# lv_io_analog_input.net
KiCad netlist of a schematic drawn in Altium Designer
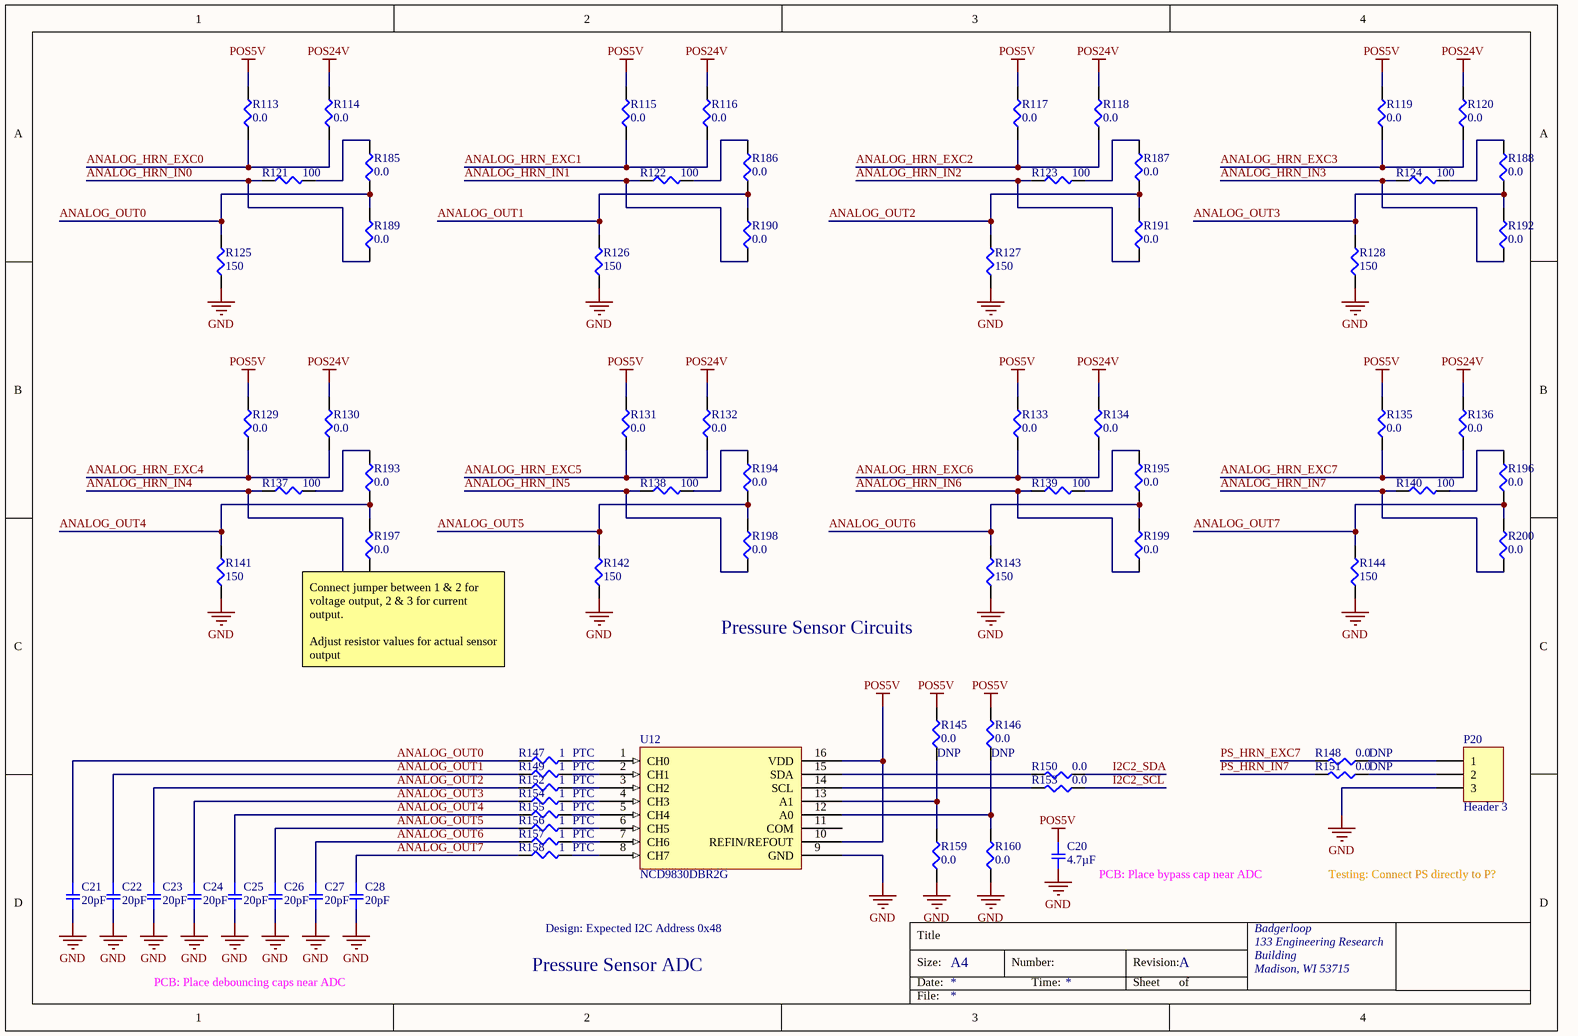
[diagram p0: lv_io_analog_input.SchDoc]

(export (version "E")
  (design (tool "Eeschema 10.0.6"))
  (components
    (comp (ref "C20")
      (value "4.7µF")
      (footprint "SMD-0805C")
      (description "CAP CER 4.7UF 6.3V X5R 0805")
      (fields
        (field (name "DIGI-KEY PART NUMBER") "490-9749-1-ND")
        (field (name "PART NUMBER") "GRM21BR60J475KA11L")
      )
      (libsource (lib "capacitor") (part "GRM21BR60J475KA11L"))
    )
    (comp (ref "C21")
      (value "20pF")
      (footprint "SMD-0402C")
      (description "CAP CER 20PF 50V NP0 0402")
      (fields
        (field (name "DIGI-KEY PART NUMBER") "490-3120-1-ND")
        (field (name "PART NUMBER") "GJM1555C1H200JB01D")
      )
      (libsource (lib "capacitor") (part "GJM1555C1H200JB01D"))
    )
    (comp (ref "C22")
      (value "20pF")
      (footprint "SMD-0402C")
      (description "CAP CER 20PF 50V NP0 0402")
      (fields
        (field (name "DIGI-KEY PART NUMBER") "490-3120-1-ND")
        (field (name "PART NUMBER") "GJM1555C1H200JB01D")
      )
      (libsource (lib "capacitor") (part "GJM1555C1H200JB01D"))
    )
    (comp (ref "C23")
      (value "20pF")
      (footprint "SMD-0402C")
      (description "CAP CER 20PF 50V NP0 0402")
      (fields
        (field (name "DIGI-KEY PART NUMBER") "490-3120-1-ND")
        (field (name "PART NUMBER") "GJM1555C1H200JB01D")
      )
      (libsource (lib "capacitor") (part "GJM1555C1H200JB01D"))
    )
    (comp (ref "C24")
      (value "20pF")
      (footprint "SMD-0402C")
      (description "CAP CER 20PF 50V NP0 0402")
      (fields
        (field (name "DIGI-KEY PART NUMBER") "490-3120-1-ND")
        (field (name "PART NUMBER") "GJM1555C1H200JB01D")
      )
      (libsource (lib "capacitor") (part "GJM1555C1H200JB01D"))
    )
    (comp (ref "C25")
      (value "20pF")
      (footprint "SMD-0402C")
      (description "CAP CER 20PF 50V NP0 0402")
      (fields
        (field (name "DIGI-KEY PART NUMBER") "490-3120-1-ND")
        (field (name "PART NUMBER") "GJM1555C1H200JB01D")
      )
      (libsource (lib "capacitor") (part "GJM1555C1H200JB01D"))
    )
    (comp (ref "C26")
      (value "20pF")
      (footprint "SMD-0402C")
      (description "CAP CER 20PF 50V NP0 0402")
      (fields
        (field (name "DIGI-KEY PART NUMBER") "490-3120-1-ND")
        (field (name "PART NUMBER") "GJM1555C1H200JB01D")
      )
      (libsource (lib "capacitor") (part "GJM1555C1H200JB01D"))
    )
    (comp (ref "C27")
      (value "20pF")
      (footprint "SMD-0402C")
      (description "CAP CER 20PF 50V NP0 0402")
      (fields
        (field (name "DIGI-KEY PART NUMBER") "490-3120-1-ND")
        (field (name "PART NUMBER") "GJM1555C1H200JB01D")
      )
      (libsource (lib "capacitor") (part "GJM1555C1H200JB01D"))
    )
    (comp (ref "C28")
      (value "20pF")
      (footprint "SMD-0402C")
      (description "CAP CER 20PF 50V NP0 0402")
      (fields
        (field (name "DIGI-KEY PART NUMBER") "490-3120-1-ND")
        (field (name "PART NUMBER") "GJM1555C1H200JB01D")
      )
      (libsource (lib "capacitor") (part "GJM1555C1H200JB01D"))
    )
    (comp (ref "P20")
      (value "Header 3")
      (footprint "Pin Header 1x3 TH Pitch 2.54mm")
      (description "Header, 3-Pin")
      (fields (field (name "PUBLISHER") "Altium Limited"))
      (libsource (lib "connector") (part "Header 3"))
    )
    (comp (ref "R113")
      (value "0.0")
      (footprint "SMD-0402-RES")
      (description "RES SMD 0.0OHM JUMPER 1/10W 0402")
      (fields (field (name "PART NUMBER") "ERJ-2GE0R00X") (field (name "DIGI-KEY PART NUMBER") "P0.0JCT-ND"))
      (libsource (lib "resistor") (part "ERJ-2GE0R00X"))
    )
    (comp (ref "R114")
      (value "0.0")
      (footprint "SMD-0402-RES")
      (description "RES SMD 0.0OHM JUMPER 1/10W 0402")
      (fields (field (name "PART NUMBER") "ERJ-2GE0R00X") (field (name "DIGI-KEY PART NUMBER") "P0.0JCT-ND"))
      (libsource (lib "resistor") (part "ERJ-2GE0R00X"))
    )
    (comp (ref "R115")
      (value "0.0")
      (footprint "SMD-0402-RES")
      (description "RES SMD 0.0OHM JUMPER 1/10W 0402")
      (fields (field (name "PART NUMBER") "ERJ-2GE0R00X") (field (name "DIGI-KEY PART NUMBER") "P0.0JCT-ND"))
      (libsource (lib "resistor") (part "ERJ-2GE0R00X"))
    )
    (comp (ref "R116")
      (value "0.0")
      (footprint "SMD-0402-RES")
      (description "RES SMD 0.0OHM JUMPER 1/10W 0402")
      (fields (field (name "PART NUMBER") "ERJ-2GE0R00X") (field (name "DIGI-KEY PART NUMBER") "P0.0JCT-ND"))
      (libsource (lib "resistor") (part "ERJ-2GE0R00X"))
    )
    (comp (ref "R117")
      (value "0.0")
      (footprint "SMD-0402-RES")
      (description "RES SMD 0.0OHM JUMPER 1/10W 0402")
      (fields (field (name "PART NUMBER") "ERJ-2GE0R00X") (field (name "DIGI-KEY PART NUMBER") "P0.0JCT-ND"))
      (libsource (lib "resistor") (part "ERJ-2GE0R00X"))
    )
    (comp (ref "R118")
      (value "0.0")
      (footprint "SMD-0402-RES")
      (description "RES SMD 0.0OHM JUMPER 1/10W 0402")
      (fields (field (name "PART NUMBER") "ERJ-2GE0R00X") (field (name "DIGI-KEY PART NUMBER") "P0.0JCT-ND"))
      (libsource (lib "resistor") (part "ERJ-2GE0R00X"))
    )
    (comp (ref "R119")
      (value "0.0")
      (footprint "SMD-0402-RES")
      (description "RES SMD 0.0OHM JUMPER 1/10W 0402")
      (fields (field (name "PART NUMBER") "ERJ-2GE0R00X") (field (name "DIGI-KEY PART NUMBER") "P0.0JCT-ND"))
      (libsource (lib "resistor") (part "ERJ-2GE0R00X"))
    )
    (comp (ref "R120")
      (value "0.0")
      (footprint "SMD-0402-RES")
      (description "RES SMD 0.0OHM JUMPER 1/10W 0402")
      (fields (field (name "PART NUMBER") "ERJ-2GE0R00X") (field (name "DIGI-KEY PART NUMBER") "P0.0JCT-ND"))
      (libsource (lib "resistor") (part "ERJ-2GE0R00X"))
    )
    (comp (ref "R121")
      (value "100")
      (footprint "SMD-0402-RES")
      (description "RES SMD 100 OHM 5% 1/10W 0402")
      (fields (field (name "PART NUMBER") "ERJ-2GEJ101X") (field (name "DIGI-KEY PART NUMBER") "P100JCT-ND"))
      (libsource (lib "resistor") (part "ERJ-2GEJ101X"))
    )
    (comp (ref "R122")
      (value "100")
      (footprint "SMD-0402-RES")
      (description "RES SMD 100 OHM 5% 1/10W 0402")
      (fields (field (name "PART NUMBER") "ERJ-2GEJ101X") (field (name "DIGI-KEY PART NUMBER") "P100JCT-ND"))
      (libsource (lib "resistor") (part "ERJ-2GEJ101X"))
    )
    (comp (ref "R123")
      (value "100")
      (footprint "SMD-0402-RES")
      (description "RES SMD 100 OHM 5% 1/10W 0402")
      (fields (field (name "PART NUMBER") "ERJ-2GEJ101X") (field (name "DIGI-KEY PART NUMBER") "P100JCT-ND"))
      (libsource (lib "resistor") (part "ERJ-2GEJ101X"))
    )
    (comp (ref "R124")
      (value "100")
      (footprint "SMD-0402-RES")
      (description "RES SMD 100 OHM 5% 1/10W 0402")
      (fields (field (name "PART NUMBER") "ERJ-2GEJ101X") (field (name "DIGI-KEY PART NUMBER") "P100JCT-ND"))
      (libsource (lib "resistor") (part "ERJ-2GEJ101X"))
    )
    (comp (ref "R125")
      (value "150")
      (footprint "SMD-0603-RES")
      (description "RES SMD 150 OHM 0.5% 1/5W 0603")
      (fields
        (field (name "PART NUMBER") "ERJ-P03D1500V")
        (field (name "DIGI-KEY PART NUMBER") "P16013CT-ND")
      )
      (libsource (lib "resistor") (part "ERJ-P03D1500V"))
    )
    (comp (ref "R126")
      (value "150")
      (footprint "SMD-0603-RES")
      (description "RES SMD 150 OHM 0.5% 1/5W 0603")
      (fields
        (field (name "PART NUMBER") "ERJ-P03D1500V")
        (field (name "DIGI-KEY PART NUMBER") "P16013CT-ND")
      )
      (libsource (lib "resistor") (part "ERJ-P03D1500V"))
    )
    (comp (ref "R127")
      (value "150")
      (footprint "SMD-0603-RES")
      (description "RES SMD 150 OHM 0.5% 1/5W 0603")
      (fields
        (field (name "PART NUMBER") "ERJ-P03D1500V")
        (field (name "DIGI-KEY PART NUMBER") "P16013CT-ND")
      )
      (libsource (lib "resistor") (part "ERJ-P03D1500V"))
    )
    (comp (ref "R128")
      (value "150")
      (footprint "SMD-0603-RES")
      (description "RES SMD 150 OHM 0.5% 1/5W 0603")
      (fields
        (field (name "PART NUMBER") "ERJ-P03D1500V")
        (field (name "DIGI-KEY PART NUMBER") "P16013CT-ND")
      )
      (libsource (lib "resistor") (part "ERJ-P03D1500V"))
    )
    (comp (ref "R129")
      (value "0.0")
      (footprint "SMD-0402-RES")
      (description "RES SMD 0.0OHM JUMPER 1/10W 0402")
      (fields (field (name "PART NUMBER") "ERJ-2GE0R00X") (field (name "DIGI-KEY PART NUMBER") "P0.0JCT-ND"))
      (libsource (lib "resistor") (part "ERJ-2GE0R00X"))
    )
    (comp (ref "R130")
      (value "0.0")
      (footprint "SMD-0402-RES")
      (description "RES SMD 0.0OHM JUMPER 1/10W 0402")
      (fields (field (name "PART NUMBER") "ERJ-2GE0R00X") (field (name "DIGI-KEY PART NUMBER") "P0.0JCT-ND"))
      (libsource (lib "resistor") (part "ERJ-2GE0R00X"))
    )
    (comp (ref "R131")
      (value "0.0")
      (footprint "SMD-0402-RES")
      (description "RES SMD 0.0OHM JUMPER 1/10W 0402")
      (fields (field (name "PART NUMBER") "ERJ-2GE0R00X") (field (name "DIGI-KEY PART NUMBER") "P0.0JCT-ND"))
      (libsource (lib "resistor") (part "ERJ-2GE0R00X"))
    )
    (comp (ref "R132")
      (value "0.0")
      (footprint "SMD-0402-RES")
      (description "RES SMD 0.0OHM JUMPER 1/10W 0402")
      (fields (field (name "PART NUMBER") "ERJ-2GE0R00X") (field (name "DIGI-KEY PART NUMBER") "P0.0JCT-ND"))
      (libsource (lib "resistor") (part "ERJ-2GE0R00X"))
    )
    (comp (ref "R133")
      (value "0.0")
      (footprint "SMD-0402-RES")
      (description "RES SMD 0.0OHM JUMPER 1/10W 0402")
      (fields (field (name "PART NUMBER") "ERJ-2GE0R00X") (field (name "DIGI-KEY PART NUMBER") "P0.0JCT-ND"))
      (libsource (lib "resistor") (part "ERJ-2GE0R00X"))
    )
    (comp (ref "R134")
      (value "0.0")
      (footprint "SMD-0402-RES")
      (description "RES SMD 0.0OHM JUMPER 1/10W 0402")
      (fields (field (name "PART NUMBER") "ERJ-2GE0R00X") (field (name "DIGI-KEY PART NUMBER") "P0.0JCT-ND"))
      (libsource (lib "resistor") (part "ERJ-2GE0R00X"))
    )
    (comp (ref "R135")
      (value "0.0")
      (footprint "SMD-0402-RES")
      (description "RES SMD 0.0OHM JUMPER 1/10W 0402")
      (fields (field (name "PART NUMBER") "ERJ-2GE0R00X") (field (name "DIGI-KEY PART NUMBER") "P0.0JCT-ND"))
      (libsource (lib "resistor") (part "ERJ-2GE0R00X"))
    )
    (comp (ref "R136")
      (value "0.0")
      (footprint "SMD-0402-RES")
      (description "RES SMD 0.0OHM JUMPER 1/10W 0402")
      (fields (field (name "PART NUMBER") "ERJ-2GE0R00X") (field (name "DIGI-KEY PART NUMBER") "P0.0JCT-ND"))
      (libsource (lib "resistor") (part "ERJ-2GE0R00X"))
    )
    (comp (ref "R137")
      (value "100")
      (footprint "SMD-0402-RES")
      (description "RES SMD 100 OHM 5% 1/10W 0402")
      (fields (field (name "PART NUMBER") "ERJ-2GEJ101X") (field (name "DIGI-KEY PART NUMBER") "P100JCT-ND"))
      (libsource (lib "resistor") (part "ERJ-2GEJ101X"))
    )
    (comp (ref "R138")
      (value "100")
      (footprint "SMD-0402-RES")
      (description "RES SMD 100 OHM 5% 1/10W 0402")
      (fields (field (name "PART NUMBER") "ERJ-2GEJ101X") (field (name "DIGI-KEY PART NUMBER") "P100JCT-ND"))
      (libsource (lib "resistor") (part "ERJ-2GEJ101X"))
    )
    (comp (ref "R139")
      (value "100")
      (footprint "SMD-0402-RES")
      (description "RES SMD 100 OHM 5% 1/10W 0402")
      (fields (field (name "PART NUMBER") "ERJ-2GEJ101X") (field (name "DIGI-KEY PART NUMBER") "P100JCT-ND"))
      (libsource (lib "resistor") (part "ERJ-2GEJ101X"))
    )
    (comp (ref "R140")
      (value "100")
      (footprint "SMD-0402-RES")
      (description "RES SMD 100 OHM 5% 1/10W 0402")
      (fields (field (name "PART NUMBER") "ERJ-2GEJ101X") (field (name "DIGI-KEY PART NUMBER") "P100JCT-ND"))
      (libsource (lib "resistor") (part "ERJ-2GEJ101X"))
    )
    (comp (ref "R141")
      (value "150")
      (footprint "SMD-0603-RES")
      (description "RES SMD 150 OHM 0.5% 1/5W 0603")
      (fields
        (field (name "PART NUMBER") "ERJ-P03D1500V")
        (field (name "DIGI-KEY PART NUMBER") "P16013CT-ND")
      )
      (libsource (lib "resistor") (part "ERJ-P03D1500V"))
    )
    (comp (ref "R142")
      (value "150")
      (footprint "SMD-0603-RES")
      (description "RES SMD 150 OHM 0.5% 1/5W 0603")
      (fields
        (field (name "PART NUMBER") "ERJ-P03D1500V")
        (field (name "DIGI-KEY PART NUMBER") "P16013CT-ND")
      )
      (libsource (lib "resistor") (part "ERJ-P03D1500V"))
    )
    (comp (ref "R143")
      (value "150")
      (footprint "SMD-0603-RES")
      (description "RES SMD 150 OHM 0.5% 1/5W 0603")
      (fields
        (field (name "PART NUMBER") "ERJ-P03D1500V")
        (field (name "DIGI-KEY PART NUMBER") "P16013CT-ND")
      )
      (libsource (lib "resistor") (part "ERJ-P03D1500V"))
    )
    (comp (ref "R144")
      (value "150")
      (footprint "SMD-0603-RES")
      (description "RES SMD 150 OHM 0.5% 1/5W 0603")
      (fields
        (field (name "PART NUMBER") "ERJ-P03D1500V")
        (field (name "DIGI-KEY PART NUMBER") "P16013CT-ND")
      )
      (libsource (lib "resistor") (part "ERJ-P03D1500V"))
    )
    (comp (ref "R145")
      (value "0.0")
      (footprint "SMD-0402-RES")
      (description "RES SMD 0.0OHM JUMPER 1/10W 0402")
      (fields
        (field (name "PART NUMBER") "ERJ-2GE0R00X")
        (field (name "DIGI-KEY PART NUMBER") "P0.0JCT-ND")
        (field (name "DNP") "DNP")
      )
      (libsource (lib "resistor") (part "ERJ-2GE0R00X"))
    )
    (comp (ref "R146")
      (value "0.0")
      (footprint "SMD-0402-RES")
      (description "RES SMD 0.0OHM JUMPER 1/10W 0402")
      (fields
        (field (name "PART NUMBER") "ERJ-2GE0R00X")
        (field (name "DIGI-KEY PART NUMBER") "P0.0JCT-ND")
        (field (name "DNP") "DNP")
      )
      (libsource (lib "resistor") (part "ERJ-2GE0R00X"))
    )
    (comp (ref "R147")
      (value "1")
      (footprint "SMD-0603-RES")
      (description "PTC RESET FUSE 6V 330MA 0603")
      (fields
        (field (name "DIGI-KEY PART NUMBER") "490-8505-1-ND")
        (field (name "MANUFACTURER") "Murata")
        (field (name "FEATURES") "PTC")
      )
      (libsource (lib "temp") (part "PRG18BB470MB1RB"))
    )
    (comp (ref "R148")
      (value "0.0")
      (footprint "SMD-0402-RES")
      (description "RES SMD 0.0OHM JUMPER 1/10W 0402")
      (fields
        (field (name "PART NUMBER") "ERJ-2GE0R00X")
        (field (name "DIGI-KEY PART NUMBER") "P0.0JCT-ND")
        (field (name "DNP") "DNP")
      )
      (libsource (lib "resistor") (part "ERJ-2GE0R00X"))
    )
    (comp (ref "R149")
      (value "1")
      (footprint "SMD-0603-RES")
      (description "PTC RESET FUSE 6V 330MA 0603")
      (fields
        (field (name "DIGI-KEY PART NUMBER") "490-8505-1-ND")
        (field (name "MANUFACTURER") "Murata")
        (field (name "FEATURES") "PTC")
      )
      (libsource (lib "temp") (part "PRG18BB470MB1RB"))
    )
    (comp (ref "R150")
      (value "0.0")
      (footprint "SMD-0402-RES")
      (description "RES SMD 0.0OHM JUMPER 1/10W 0402")
      (fields (field (name "PART NUMBER") "ERJ-2GE0R00X") (field (name "DIGI-KEY PART NUMBER") "P0.0JCT-ND"))
      (libsource (lib "resistor") (part "ERJ-2GE0R00X"))
    )
    (comp (ref "R151")
      (value "0.0")
      (footprint "SMD-0402-RES")
      (description "RES SMD 0.0OHM JUMPER 1/10W 0402")
      (fields
        (field (name "PART NUMBER") "ERJ-2GE0R00X")
        (field (name "DIGI-KEY PART NUMBER") "P0.0JCT-ND")
        (field (name "DNP") "DNP")
      )
      (libsource (lib "") (part "ERJ-2GE0R00X_1"))
    )
    (comp (ref "R152")
      (value "1")
      (footprint "SMD-0603-RES")
      (description "PTC RESET FUSE 6V 330MA 0603")
      (fields
        (field (name "DIGI-KEY PART NUMBER") "490-8505-1-ND")
        (field (name "MANUFACTURER") "Murata")
        (field (name "FEATURES") "PTC")
      )
      (libsource (lib "temp") (part "PRG18BB470MB1RB"))
    )
    (comp (ref "R153")
      (value "0.0")
      (footprint "SMD-0402-RES")
      (description "RES SMD 0.0OHM JUMPER 1/10W 0402")
      (fields (field (name "PART NUMBER") "ERJ-2GE0R00X") (field (name "DIGI-KEY PART NUMBER") "P0.0JCT-ND"))
      (libsource (lib "resistor") (part "ERJ-2GE0R00X"))
    )
    (comp (ref "R154")
      (value "1")
      (footprint "SMD-0603-RES")
      (description "PTC RESET FUSE 6V 330MA 0603")
      (fields
        (field (name "DIGI-KEY PART NUMBER") "490-8505-1-ND")
        (field (name "MANUFACTURER") "Murata")
        (field (name "FEATURES") "PTC")
      )
      (libsource (lib "temp") (part "PRG18BB470MB1RB"))
    )
    (comp (ref "R155")
      (value "1")
      (footprint "SMD-0603-RES")
      (description "PTC RESET FUSE 6V 330MA 0603")
      (fields
        (field (name "DIGI-KEY PART NUMBER") "490-8505-1-ND")
        (field (name "MANUFACTURER") "Murata")
        (field (name "FEATURES") "PTC")
      )
      (libsource (lib "temp") (part "PRG18BB470MB1RB"))
    )
    (comp (ref "R156")
      (value "1")
      (footprint "SMD-0603-RES")
      (description "PTC RESET FUSE 6V 330MA 0603")
      (fields
        (field (name "DIGI-KEY PART NUMBER") "490-8505-1-ND")
        (field (name "MANUFACTURER") "Murata")
        (field (name "FEATURES") "PTC")
      )
      (libsource (lib "temp") (part "PRG18BB470MB1RB"))
    )
    (comp (ref "R157")
      (value "1")
      (footprint "SMD-0603-RES")
      (description "PTC RESET FUSE 6V 330MA 0603")
      (fields
        (field (name "DIGI-KEY PART NUMBER") "490-8505-1-ND")
        (field (name "MANUFACTURER") "Murata")
        (field (name "FEATURES") "PTC")
      )
      (libsource (lib "temp") (part "PRG18BB470MB1RB"))
    )
    (comp (ref "R158")
      (value "1")
      (footprint "SMD-0603-RES")
      (description "PTC RESET FUSE 6V 330MA 0603")
      (fields
        (field (name "DIGI-KEY PART NUMBER") "490-8505-1-ND")
        (field (name "MANUFACTURER") "Murata")
        (field (name "FEATURES") "PTC")
      )
      (libsource (lib "temp") (part "PRG18BB470MB1RB"))
    )
    (comp (ref "R159")
      (value "0.0")
      (footprint "SMD-0402-RES")
      (description "RES SMD 0.0OHM JUMPER 1/10W 0402")
      (fields (field (name "PART NUMBER") "ERJ-2GE0R00X") (field (name "DIGI-KEY PART NUMBER") "P0.0JCT-ND"))
      (libsource (lib "resistor") (part "ERJ-2GE0R00X"))
    )
    (comp (ref "R160")
      (value "0.0")
      (footprint "SMD-0402-RES")
      (description "RES SMD 0.0OHM JUMPER 1/10W 0402")
      (fields (field (name "PART NUMBER") "ERJ-2GE0R00X") (field (name "DIGI-KEY PART NUMBER") "P0.0JCT-ND"))
      (libsource (lib "resistor") (part "ERJ-2GE0R00X"))
    )
    (comp (ref "R185")
      (value "0.0")
      (footprint "SMD-0402-RES")
      (description "RES SMD 0.0OHM JUMPER 1/10W 0402")
      (fields (field (name "PART NUMBER") "ERJ-2GE0R00X") (field (name "DIGI-KEY PART NUMBER") "P0.0JCT-ND"))
      (libsource (lib "resistor") (part "ERJ-2GE0R00X"))
    )
    (comp (ref "R186")
      (value "0.0")
      (footprint "SMD-0402-RES")
      (description "RES SMD 0.0OHM JUMPER 1/10W 0402")
      (fields (field (name "PART NUMBER") "ERJ-2GE0R00X") (field (name "DIGI-KEY PART NUMBER") "P0.0JCT-ND"))
      (libsource (lib "resistor") (part "ERJ-2GE0R00X"))
    )
    (comp (ref "R187")
      (value "0.0")
      (footprint "SMD-0402-RES")
      (description "RES SMD 0.0OHM JUMPER 1/10W 0402")
      (fields (field (name "PART NUMBER") "ERJ-2GE0R00X") (field (name "DIGI-KEY PART NUMBER") "P0.0JCT-ND"))
      (libsource (lib "resistor") (part "ERJ-2GE0R00X"))
    )
    (comp (ref "R188")
      (value "0.0")
      (footprint "SMD-0402-RES")
      (description "RES SMD 0.0OHM JUMPER 1/10W 0402")
      (fields (field (name "PART NUMBER") "ERJ-2GE0R00X") (field (name "DIGI-KEY PART NUMBER") "P0.0JCT-ND"))
      (libsource (lib "resistor") (part "ERJ-2GE0R00X"))
    )
    (comp (ref "R189")
      (value "0.0")
      (footprint "SMD-0402-RES")
      (description "RES SMD 0.0OHM JUMPER 1/10W 0402")
      (fields (field (name "PART NUMBER") "ERJ-2GE0R00X") (field (name "DIGI-KEY PART NUMBER") "P0.0JCT-ND"))
      (libsource (lib "resistor") (part "ERJ-2GE0R00X"))
    )
    (comp (ref "R190")
      (value "0.0")
      (footprint "SMD-0402-RES")
      (description "RES SMD 0.0OHM JUMPER 1/10W 0402")
      (fields (field (name "PART NUMBER") "ERJ-2GE0R00X") (field (name "DIGI-KEY PART NUMBER") "P0.0JCT-ND"))
      (libsource (lib "resistor") (part "ERJ-2GE0R00X"))
    )
    (comp (ref "R191")
      (value "0.0")
      (footprint "SMD-0402-RES")
      (description "RES SMD 0.0OHM JUMPER 1/10W 0402")
      (fields (field (name "PART NUMBER") "ERJ-2GE0R00X") (field (name "DIGI-KEY PART NUMBER") "P0.0JCT-ND"))
      (libsource (lib "resistor") (part "ERJ-2GE0R00X"))
    )
    (comp (ref "R192")
      (value "0.0")
      (footprint "SMD-0402-RES")
      (description "RES SMD 0.0OHM JUMPER 1/10W 0402")
      (fields (field (name "PART NUMBER") "ERJ-2GE0R00X") (field (name "DIGI-KEY PART NUMBER") "P0.0JCT-ND"))
      (libsource (lib "resistor") (part "ERJ-2GE0R00X"))
    )
    (comp (ref "R193")
      (value "0.0")
      (footprint "SMD-0402-RES")
      (description "RES SMD 0.0OHM JUMPER 1/10W 0402")
      (fields (field (name "PART NUMBER") "ERJ-2GE0R00X") (field (name "DIGI-KEY PART NUMBER") "P0.0JCT-ND"))
      (libsource (lib "resistor") (part "ERJ-2GE0R00X"))
    )
    (comp (ref "R194")
      (value "0.0")
      (footprint "SMD-0402-RES")
      (description "RES SMD 0.0OHM JUMPER 1/10W 0402")
      (fields (field (name "PART NUMBER") "ERJ-2GE0R00X") (field (name "DIGI-KEY PART NUMBER") "P0.0JCT-ND"))
      (libsource (lib "resistor") (part "ERJ-2GE0R00X"))
    )
    (comp (ref "R195")
      (value "0.0")
      (footprint "SMD-0402-RES")
      (description "RES SMD 0.0OHM JUMPER 1/10W 0402")
      (fields (field (name "PART NUMBER") "ERJ-2GE0R00X") (field (name "DIGI-KEY PART NUMBER") "P0.0JCT-ND"))
      (libsource (lib "resistor") (part "ERJ-2GE0R00X"))
    )
    (comp (ref "R196")
      (value "0.0")
      (footprint "SMD-0402-RES")
      (description "RES SMD 0.0OHM JUMPER 1/10W 0402")
      (fields (field (name "PART NUMBER") "ERJ-2GE0R00X") (field (name "DIGI-KEY PART NUMBER") "P0.0JCT-ND"))
      (libsource (lib "resistor") (part "ERJ-2GE0R00X"))
    )
    (comp (ref "R197")
      (value "0.0")
      (footprint "SMD-0402-RES")
      (description "RES SMD 0.0OHM JUMPER 1/10W 0402")
      (fields (field (name "PART NUMBER") "ERJ-2GE0R00X") (field (name "DIGI-KEY PART NUMBER") "P0.0JCT-ND"))
      (libsource (lib "resistor") (part "ERJ-2GE0R00X"))
    )
    (comp (ref "R198")
      (value "0.0")
      (footprint "SMD-0402-RES")
      (description "RES SMD 0.0OHM JUMPER 1/10W 0402")
      (fields (field (name "PART NUMBER") "ERJ-2GE0R00X") (field (name "DIGI-KEY PART NUMBER") "P0.0JCT-ND"))
      (libsource (lib "resistor") (part "ERJ-2GE0R00X"))
    )
    (comp (ref "R199")
      (value "0.0")
      (footprint "SMD-0402-RES")
      (description "RES SMD 0.0OHM JUMPER 1/10W 0402")
      (fields (field (name "PART NUMBER") "ERJ-2GE0R00X") (field (name "DIGI-KEY PART NUMBER") "P0.0JCT-ND"))
      (libsource (lib "resistor") (part "ERJ-2GE0R00X"))
    )
    (comp (ref "R200")
      (value "0.0")
      (footprint "SMD-0402-RES")
      (description "RES SMD 0.0OHM JUMPER 1/10W 0402")
      (fields (field (name "PART NUMBER") "ERJ-2GE0R00X") (field (name "DIGI-KEY PART NUMBER") "P0.0JCT-ND"))
      (libsource (lib "resistor") (part "ERJ-2GE0R00X"))
    )
    (comp (ref "U12")
      (value "NCD9830DBR2G")
      (footprint "TSOP65P640X120_HS-17N")
      (description "IC ADC 8BIT 8CH I2C 16TSSOP")
      (fields (field (name "MANUFACTURER") "ON Semiconductor"))
      (libsource (lib "ic") (part "NCD9830DBR2G"))
    )
  )
  (nets
    (net (code "1") (name "/ANALOG_HRN_EXC0") (class "Default")
      (node (ref "R113") (pin "1") (pinfunction "1_1") (pintype "passive"))
      (node (ref "R114") (pin "1") (pinfunction "1_1") (pintype "passive"))
    )
    (net (code "2") (name "/ANALOG_HRN_EXC1") (class "Default")
      (node (ref "R115") (pin "1") (pinfunction "1_1") (pintype "passive"))
      (node (ref "R116") (pin "1") (pinfunction "1_1") (pintype "passive"))
    )
    (net (code "3") (name "/ANALOG_HRN_EXC2") (class "Default")
      (node (ref "R117") (pin "1") (pinfunction "1_1") (pintype "passive"))
      (node (ref "R118") (pin "1") (pinfunction "1_1") (pintype "passive"))
    )
    (net (code "4") (name "/ANALOG_HRN_EXC3") (class "Default")
      (node (ref "R119") (pin "1") (pinfunction "1_1") (pintype "passive"))
      (node (ref "R120") (pin "1") (pinfunction "1_1") (pintype "passive"))
    )
    (net (code "5") (name "/ANALOG_HRN_EXC4") (class "Default")
      (node (ref "R129") (pin "1") (pinfunction "1_1") (pintype "passive"))
      (node (ref "R130") (pin "1") (pinfunction "1_1") (pintype "passive"))
    )
    (net (code "6") (name "/ANALOG_HRN_EXC5") (class "Default")
      (node (ref "R131") (pin "1") (pinfunction "1_1") (pintype "passive"))
      (node (ref "R132") (pin "1") (pinfunction "1_1") (pintype "passive"))
    )
    (net (code "7") (name "/ANALOG_HRN_EXC6") (class "Default")
      (node (ref "R133") (pin "1") (pinfunction "1_1") (pintype "passive"))
      (node (ref "R134") (pin "1") (pinfunction "1_1") (pintype "passive"))
    )
    (net (code "8") (name "/ANALOG_HRN_EXC7") (class "Default")
      (node (ref "R135") (pin "1") (pinfunction "1_1") (pintype "passive"))
      (node (ref "R136") (pin "1") (pinfunction "1_1") (pintype "passive"))
    )
    (net (code "9") (name "/ANALOG_HRN_IN0") (class "Default")
      (node (ref "R121") (pin "1") (pinfunction "1_1") (pintype "passive"))
      (node (ref "R189") (pin "1") (pinfunction "1_1") (pintype "passive"))
    )
    (net (code "10") (name "/ANALOG_HRN_IN1") (class "Default")
      (node (ref "R122") (pin "1") (pinfunction "1_1") (pintype "passive"))
      (node (ref "R190") (pin "1") (pinfunction "1_1") (pintype "passive"))
    )
    (net (code "11") (name "/ANALOG_HRN_IN2") (class "Default")
      (node (ref "R123") (pin "1") (pinfunction "1_1") (pintype "passive"))
      (node (ref "R191") (pin "1") (pinfunction "1_1") (pintype "passive"))
    )
    (net (code "12") (name "/ANALOG_HRN_IN3") (class "Default")
      (node (ref "R124") (pin "1") (pinfunction "1_1") (pintype "passive"))
      (node (ref "R192") (pin "1") (pinfunction "1_1") (pintype "passive"))
    )
    (net (code "13") (name "/ANALOG_HRN_IN4") (class "Default")
      (node (ref "R137") (pin "1") (pinfunction "1_1") (pintype "passive"))
      (node (ref "R197") (pin "1") (pinfunction "1_1") (pintype "passive"))
    )
    (net (code "14") (name "/ANALOG_HRN_IN5") (class "Default")
      (node (ref "R138") (pin "1") (pinfunction "1_1") (pintype "passive"))
      (node (ref "R198") (pin "1") (pinfunction "1_1") (pintype "passive"))
    )
    (net (code "15") (name "/ANALOG_HRN_IN6") (class "Default")
      (node (ref "R139") (pin "1") (pinfunction "1_1") (pintype "passive"))
      (node (ref "R199") (pin "1") (pinfunction "1_1") (pintype "passive"))
    )
    (net (code "16") (name "/ANALOG_HRN_IN7") (class "Default")
      (node (ref "R140") (pin "1") (pinfunction "1_1") (pintype "passive"))
      (node (ref "R200") (pin "1") (pinfunction "1_1") (pintype "passive"))
    )
    (net (code "17") (name "/ANALOG_OUT0") (class "Default")
      (node (ref "C21") (pin "1") (pinfunction "1_1") (pintype "passive"))
      (node (ref "R125") (pin "2") (pinfunction "2_2") (pintype "passive"))
      (node (ref "R147") (pin "1") (pinfunction "1_1") (pintype "passive"))
      (node (ref "R185") (pin "1") (pinfunction "1_1") (pintype "passive"))
      (node (ref "R189") (pin "2") (pinfunction "2_2") (pintype "passive"))
    )
    (net (code "18") (name "/ANALOG_OUT1") (class "Default")
      (node (ref "C22") (pin "1") (pinfunction "1_1") (pintype "passive"))
      (node (ref "R126") (pin "2") (pinfunction "2_2") (pintype "passive"))
      (node (ref "R149") (pin "1") (pinfunction "1_1") (pintype "passive"))
      (node (ref "R186") (pin "1") (pinfunction "1_1") (pintype "passive"))
      (node (ref "R190") (pin "2") (pinfunction "2_2") (pintype "passive"))
    )
    (net (code "19") (name "/ANALOG_OUT2") (class "Default")
      (node (ref "C23") (pin "1") (pinfunction "1_1") (pintype "passive"))
      (node (ref "R127") (pin "2") (pinfunction "2_2") (pintype "passive"))
      (node (ref "R152") (pin "1") (pinfunction "1_1") (pintype "passive"))
      (node (ref "R187") (pin "1") (pinfunction "1_1") (pintype "passive"))
      (node (ref "R191") (pin "2") (pinfunction "2_2") (pintype "passive"))
    )
    (net (code "20") (name "/ANALOG_OUT3") (class "Default")
      (node (ref "C24") (pin "1") (pinfunction "1_1") (pintype "passive"))
      (node (ref "R128") (pin "2") (pinfunction "2_2") (pintype "passive"))
      (node (ref "R154") (pin "1") (pinfunction "1_1") (pintype "passive"))
      (node (ref "R188") (pin "1") (pinfunction "1_1") (pintype "passive"))
      (node (ref "R192") (pin "2") (pinfunction "2_2") (pintype "passive"))
    )
    (net (code "21") (name "/ANALOG_OUT4") (class "Default")
      (node (ref "C25") (pin "1") (pinfunction "1_1") (pintype "passive"))
      (node (ref "R141") (pin "2") (pinfunction "2_2") (pintype "passive"))
      (node (ref "R155") (pin "1") (pinfunction "1_1") (pintype "passive"))
      (node (ref "R193") (pin "1") (pinfunction "1_1") (pintype "passive"))
      (node (ref "R197") (pin "2") (pinfunction "2_2") (pintype "passive"))
    )
    (net (code "22") (name "/ANALOG_OUT5") (class "Default")
      (node (ref "C26") (pin "1") (pinfunction "1_1") (pintype "passive"))
      (node (ref "R142") (pin "2") (pinfunction "2_2") (pintype "passive"))
      (node (ref "R156") (pin "1") (pinfunction "1_1") (pintype "passive"))
      (node (ref "R194") (pin "1") (pinfunction "1_1") (pintype "passive"))
      (node (ref "R198") (pin "2") (pinfunction "2_2") (pintype "passive"))
    )
    (net (code "23") (name "/ANALOG_OUT6") (class "Default")
      (node (ref "C27") (pin "1") (pinfunction "1_1") (pintype "passive"))
      (node (ref "R143") (pin "2") (pinfunction "2_2") (pintype "passive"))
      (node (ref "R157") (pin "1") (pinfunction "1_1") (pintype "passive"))
      (node (ref "R195") (pin "1") (pinfunction "1_1") (pintype "passive"))
      (node (ref "R199") (pin "2") (pinfunction "2_2") (pintype "passive"))
    )
    (net (code "24") (name "/ANALOG_OUT7") (class "Default")
      (node (ref "C28") (pin "1") (pinfunction "1_1") (pintype "passive"))
      (node (ref "R144") (pin "2") (pinfunction "2_2") (pintype "passive"))
      (node (ref "R158") (pin "1") (pinfunction "1_1") (pintype "passive"))
      (node (ref "R196") (pin "1") (pinfunction "1_1") (pintype "passive"))
      (node (ref "R200") (pin "2") (pinfunction "2_2") (pintype "passive"))
    )
    (net (code "25") (name "/I2C2_SCL") (class "Default")
      (node (ref "R153") (pin "1") (pinfunction "1_1") (pintype "passive"))
    )
    (net (code "26") (name "/I2C2_SDA") (class "Default")
      (node (ref "R150") (pin "1") (pinfunction "1_1") (pintype "passive"))
    )
    (net (code "27") (name "/PS_HRN_EXC7") (class "Default")
      (node (ref "R148") (pin "2") (pinfunction "2_2") (pintype "passive"))
    )
    (net (code "28") (name "/PS_HRN_IN7") (class "Default")
      (node (ref "R151") (pin "2") (pinfunction "2_2") (pintype "passive"))
    )
    (net (code "29") (name "GND") (class "Default")
      (node (ref "C20") (pin "2") (pinfunction "2_2") (pintype "passive"))
      (node (ref "C21") (pin "2") (pinfunction "2_2") (pintype "passive"))
      (node (ref "C22") (pin "2") (pinfunction "2_2") (pintype "passive"))
      (node (ref "C23") (pin "2") (pinfunction "2_2") (pintype "passive"))
      (node (ref "C24") (pin "2") (pinfunction "2_2") (pintype "passive"))
      (node (ref "C25") (pin "2") (pinfunction "2_2") (pintype "passive"))
      (node (ref "C26") (pin "2") (pinfunction "2_2") (pintype "passive"))
      (node (ref "C27") (pin "2") (pinfunction "2_2") (pintype "passive"))
      (node (ref "C28") (pin "2") (pinfunction "2_2") (pintype "passive"))
      (node (ref "P20") (pin "3") (pinfunction "3_3") (pintype "passive"))
      (node (ref "R125") (pin "1") (pinfunction "1_1") (pintype "passive"))
      (node (ref "R126") (pin "1") (pinfunction "1_1") (pintype "passive"))
      (node (ref "R127") (pin "1") (pinfunction "1_1") (pintype "passive"))
      (node (ref "R128") (pin "1") (pinfunction "1_1") (pintype "passive"))
      (node (ref "R141") (pin "1") (pinfunction "1_1") (pintype "passive"))
      (node (ref "R142") (pin "1") (pinfunction "1_1") (pintype "passive"))
      (node (ref "R143") (pin "1") (pinfunction "1_1") (pintype "passive"))
      (node (ref "R144") (pin "1") (pinfunction "1_1") (pintype "passive"))
      (node (ref "R159") (pin "1") (pinfunction "1_1") (pintype "passive"))
      (node (ref "R160") (pin "1") (pinfunction "1_1") (pintype "passive"))
      (node (ref "U12") (pin "9") (pinfunction "GND_9") (pintype "power_in"))
    )
    (net (code "30") (name "Net-(P20-Pad1)") (class "Default")
      (node (ref "P20") (pin "1") (pinfunction "1_1") (pintype "passive"))
      (node (ref "R148") (pin "1") (pinfunction "1_1") (pintype "passive"))
    )
    (net (code "31") (name "Net-(P20-Pad2)") (class "Default")
      (node (ref "P20") (pin "2") (pinfunction "2_2") (pintype "passive"))
      (node (ref "R151") (pin "1") (pinfunction "1_1") (pintype "passive"))
    )
    (net (code "32") (name "Net-(R121-Pad2)") (class "Default")
      (node (ref "R121") (pin "2") (pinfunction "2_2") (pintype "passive"))
      (node (ref "R185") (pin "2") (pinfunction "2_2") (pintype "passive"))
    )
    (net (code "33") (name "Net-(R122-Pad2)") (class "Default")
      (node (ref "R122") (pin "2") (pinfunction "2_2") (pintype "passive"))
      (node (ref "R186") (pin "2") (pinfunction "2_2") (pintype "passive"))
    )
    (net (code "34") (name "Net-(R123-Pad2)") (class "Default")
      (node (ref "R123") (pin "2") (pinfunction "2_2") (pintype "passive"))
      (node (ref "R187") (pin "2") (pinfunction "2_2") (pintype "passive"))
    )
    (net (code "35") (name "Net-(R124-Pad2)") (class "Default")
      (node (ref "R124") (pin "2") (pinfunction "2_2") (pintype "passive"))
      (node (ref "R188") (pin "2") (pinfunction "2_2") (pintype "passive"))
    )
    (net (code "36") (name "Net-(R137-Pad2)") (class "Default")
      (node (ref "R137") (pin "2") (pinfunction "2_2") (pintype "passive"))
      (node (ref "R193") (pin "2") (pinfunction "2_2") (pintype "passive"))
    )
    (net (code "37") (name "Net-(R138-Pad2)") (class "Default")
      (node (ref "R138") (pin "2") (pinfunction "2_2") (pintype "passive"))
      (node (ref "R194") (pin "2") (pinfunction "2_2") (pintype "passive"))
    )
    (net (code "38") (name "Net-(R139-Pad2)") (class "Default")
      (node (ref "R139") (pin "2") (pinfunction "2_2") (pintype "passive"))
      (node (ref "R195") (pin "2") (pinfunction "2_2") (pintype "passive"))
    )
    (net (code "39") (name "Net-(R140-Pad2)") (class "Default")
      (node (ref "R140") (pin "2") (pinfunction "2_2") (pintype "passive"))
      (node (ref "R196") (pin "2") (pinfunction "2_2") (pintype "passive"))
    )
    (net (code "40") (name "Net-(U12-A0)") (class "Default")
      (node (ref "R146") (pin "1") (pinfunction "1_1") (pintype "passive"))
      (node (ref "R160") (pin "2") (pinfunction "2_2") (pintype "passive"))
      (node (ref "U12") (pin "12") (pinfunction "A0_12") (pintype "passive"))
    )
    (net (code "41") (name "Net-(U12-A1)") (class "Default")
      (node (ref "R145") (pin "1") (pinfunction "1_1") (pintype "passive"))
      (node (ref "R159") (pin "2") (pinfunction "2_2") (pintype "passive"))
      (node (ref "U12") (pin "13") (pinfunction "A1_13") (pintype "passive"))
    )
    (net (code "42") (name "Net-(U12-CH0)") (class "Default")
      (node (ref "R147") (pin "2") (pinfunction "2_2") (pintype "passive"))
      (node (ref "U12") (pin "1") (pinfunction "CH0_1") (pintype "input"))
    )
    (net (code "43") (name "Net-(U12-CH1)") (class "Default")
      (node (ref "R149") (pin "2") (pinfunction "2_2") (pintype "passive"))
      (node (ref "U12") (pin "2") (pinfunction "CH1_2") (pintype "input"))
    )
    (net (code "44") (name "Net-(U12-CH2)") (class "Default")
      (node (ref "R152") (pin "2") (pinfunction "2_2") (pintype "passive"))
      (node (ref "U12") (pin "3") (pinfunction "CH2_3") (pintype "input"))
    )
    (net (code "45") (name "Net-(U12-CH3)") (class "Default")
      (node (ref "R154") (pin "2") (pinfunction "2_2") (pintype "passive"))
      (node (ref "U12") (pin "4") (pinfunction "CH3_4") (pintype "input"))
    )
    (net (code "46") (name "Net-(U12-CH4)") (class "Default")
      (node (ref "R155") (pin "2") (pinfunction "2_2") (pintype "passive"))
      (node (ref "U12") (pin "5") (pinfunction "CH4_5") (pintype "input"))
    )
    (net (code "47") (name "Net-(U12-CH5)") (class "Default")
      (node (ref "R156") (pin "2") (pinfunction "2_2") (pintype "passive"))
      (node (ref "U12") (pin "6") (pinfunction "CH5_6") (pintype "input"))
    )
    (net (code "48") (name "Net-(U12-CH6)") (class "Default")
      (node (ref "R157") (pin "2") (pinfunction "2_2") (pintype "passive"))
      (node (ref "U12") (pin "7") (pinfunction "CH6_7") (pintype "input"))
    )
    (net (code "49") (name "Net-(U12-CH7)") (class "Default")
      (node (ref "R158") (pin "2") (pinfunction "2_2") (pintype "passive"))
      (node (ref "U12") (pin "8") (pinfunction "CH7_8") (pintype "input"))
    )
    (net (code "50") (name "Net-(U12-SCL)") (class "Default")
      (node (ref "R153") (pin "2") (pinfunction "2_2") (pintype "passive"))
      (node (ref "U12") (pin "14") (pinfunction "SCL_14") (pintype "passive"))
    )
    (net (code "51") (name "Net-(U12-SDA)") (class "Default")
      (node (ref "R150") (pin "2") (pinfunction "2_2") (pintype "passive"))
      (node (ref "U12") (pin "15") (pinfunction "SDA_15") (pintype "passive"))
    )
    (net (code "52") (name "POS5V") (class "Default")
      (node (ref "C20") (pin "1") (pinfunction "1_1") (pintype "passive"))
      (node (ref "R113") (pin "2") (pinfunction "2_2") (pintype "passive"))
      (node (ref "R115") (pin "2") (pinfunction "2_2") (pintype "passive"))
      (node (ref "R117") (pin "2") (pinfunction "2_2") (pintype "passive"))
      (node (ref "R119") (pin "2") (pinfunction "2_2") (pintype "passive"))
      (node (ref "R129") (pin "2") (pinfunction "2_2") (pintype "passive"))
      (node (ref "R131") (pin "2") (pinfunction "2_2") (pintype "passive"))
      (node (ref "R133") (pin "2") (pinfunction "2_2") (pintype "passive"))
      (node (ref "R135") (pin "2") (pinfunction "2_2") (pintype "passive"))
      (node (ref "R145") (pin "2") (pinfunction "2_2") (pintype "passive"))
      (node (ref "R146") (pin "2") (pinfunction "2_2") (pintype "passive"))
      (node (ref "U12") (pin "10") (pinfunction "REFIN/REFOUT_10") (pintype "power_in"))
      (node (ref "U12") (pin "16") (pinfunction "VDD_16") (pintype "power_in"))
    )
    (net (code "53") (name "POS24V") (class "Default")
      (node (ref "R114") (pin "2") (pinfunction "2_2") (pintype "passive"))
      (node (ref "R116") (pin "2") (pinfunction "2_2") (pintype "passive"))
      (node (ref "R118") (pin "2") (pinfunction "2_2") (pintype "passive"))
      (node (ref "R120") (pin "2") (pinfunction "2_2") (pintype "passive"))
      (node (ref "R130") (pin "2") (pinfunction "2_2") (pintype "passive"))
      (node (ref "R132") (pin "2") (pinfunction "2_2") (pintype "passive"))
      (node (ref "R134") (pin "2") (pinfunction "2_2") (pintype "passive"))
      (node (ref "R136") (pin "2") (pinfunction "2_2") (pintype "passive"))
    )
    (net (code "54") (name "unconnected-(U12-COM-Pad11)") (class "Default")
      (node (ref "U12") (pin "11") (pinfunction "COM_11") (pintype "power_in"))
    )
  )
)
